# 30V_to_1V8.net
KiCad netlist of a schematic drawn in EAGLE
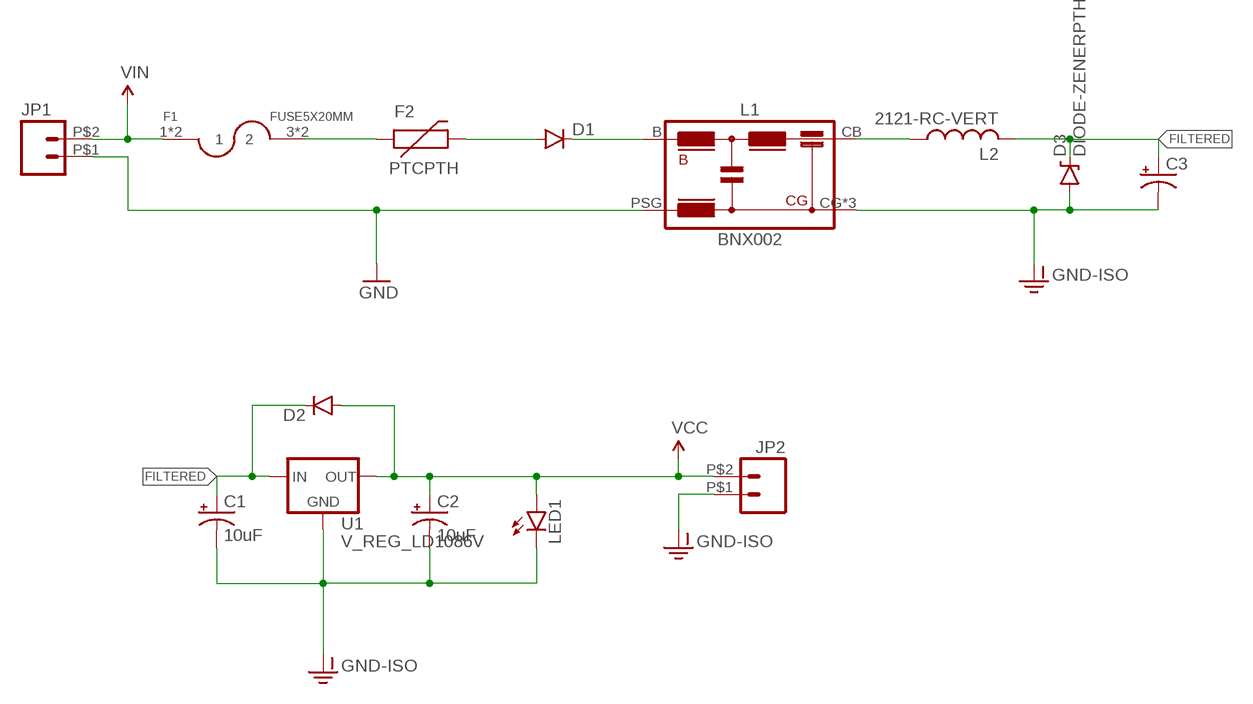
[diagram p0: schematic, sheet 1]

(export (version "E")
  (design (tool "Eeschema 10.0.6"))
  (components
    (comp (ref "C1")
      (value "10uF")
      (footprint "eagle-import:KEMET_E")
      (libsource (lib "eagle-import") (part "10UF-50V-10%(PTH)"))
    )
    (comp (ref "C2")
      (value "10uF")
      (footprint "eagle-import:KEMET_E")
      (libsource (lib "eagle-import") (part "10UF-50V-10%(PTH)"))
    )
    (comp (ref "C3")
      (value "CPOL-USE10-30")
      (footprint "eagle-import:EB30D")
      (libsource (lib "eagle-import") (part "CPOL-USE10-30"))
    )
    (comp (ref "D1")
      (value "DIODEPTH")
      (footprint "eagle-import:DIODE-1N4001")
      (libsource (lib "eagle-import") (part "DIODEPTH"))
    )
    (comp (ref "D2")
      (value "DIODEPTH")
      (footprint "eagle-import:DIODE-1N4001")
      (libsource (lib "eagle-import") (part "DIODEPTH"))
    )
    (comp (ref "D3")
      (value "DIODE-ZENERPTH")
      (footprint "eagle-import:DIODE-ZENER")
      (libsource (lib "eagle-import") (part "DIODE-ZENERPTH"))
    )
    (comp (ref "F1")
      (value "FUSE5X20MM")
      (footprint "eagle-import:FUSE_1A3399")
      (libsource (lib "eagle-import") (part "FUSE5X20MM"))
    )
    (comp (ref "F2")
      (value "PTCPTH")
      (footprint "eagle-import:PTC")
      (libsource (lib "eagle-import") (part "PTCPTH"))
    )
    (comp (ref "JP1")
      (value "M02TE-282834-2")
      (footprint "eagle-import:1X02_282834-2")
      (libsource (lib "eagle-import") (part "M02TE-282834-2"))
    )
    (comp (ref "JP2")
      (value "M02TE-282834-2")
      (footprint "eagle-import:1X02_282834-2")
      (libsource (lib "eagle-import") (part "M02TE-282834-2"))
    )
    (comp (ref "L1")
      (value "BNX002")
      (footprint "eagle-import:BNX002")
      (libsource (lib "eagle-import") (part "BNX002"))
    )
    (comp (ref "L2")
      (value "2121-RC-VERT")
      (footprint "eagle-import:2121-RC-VERT")
      (libsource (lib "eagle-import") (part "2121-RC-VERT"))
    )
    (comp (ref "LED1")
      (value "LED5MM")
      (footprint "eagle-import:LED5MM")
      (libsource (lib "eagle-import") (part "LED5MM"))
    )
    (comp (ref "U1")
      (value "V_REG_LD1086V")
      (footprint "eagle-import:TO-220-SINGLE")
      (libsource (lib "eagle-import") (part "V_REG_LD1086V"))
    )
  )
  (nets
    (net (code "1") (name "FILTERED") (class "Default")
      (node (ref "C1") (pin "+") (pinfunction "+_+") (pintype "passive"))
      (node (ref "C3") (pin "+") (pinfunction "+_+") (pintype "passive"))
      (node (ref "D2") (pin "C") (pinfunction "C_C") (pintype "passive"))
      (node (ref "D3") (pin "P$1") (pinfunction "C_P$1") (pintype "passive"))
      (node (ref "L2") (pin "2") (pinfunction "2_2") (pintype "passive"))
      (node (ref "U1") (pin "IN") (pinfunction "IN_IN") (pintype "input"))
    )
    (net (code "2") (name "GND") (class "Default")
      (node (ref "JP1") (pin "P$1") (pinfunction "1_P$1") (pintype "passive"))
      (node (ref "L1") (pin "PSG") (pinfunction "PSG_PSG") (pintype "passive"))
    )
    (net (code "3") (name "GND-ISO") (class "Default")
      (node (ref "C1") (pin "-") (pinfunction "-_-") (pintype "passive"))
      (node (ref "C2") (pin "-") (pinfunction "-_-") (pintype "passive"))
      (node (ref "C3") (pin "-") (pinfunction "-_-") (pintype "passive"))
      (node (ref "D3") (pin "P$2") (pinfunction "A_P$2") (pintype "passive"))
      (node (ref "JP2") (pin "P$1") (pinfunction "1_P$1") (pintype "passive"))
      (node (ref "L1") (pin "CG") (pinfunction "CG_CG") (pintype "passive"))
      (node (ref "L1") (pin "CG1") (pinfunction "CG_CG1") (pintype "passive"))
      (node (ref "L1") (pin "CG2") (pinfunction "CG_CG2") (pintype "passive"))
      (node (ref "LED1") (pin "K") (pinfunction "C_K") (pintype "passive"))
      (node (ref "U1") (pin "GND") (pinfunction "GND_GND") (pintype "passive"))
    )
    (net (code "4") (name "Net-(D1-PadC)") (class "Default")
      (node (ref "D1") (pin "C") (pinfunction "C_C") (pintype "passive"))
      (node (ref "L1") (pin "B") (pinfunction "B_B") (pintype "passive"))
    )
    (net (code "5") (name "Net-(F2-1)") (class "Default")
      (node (ref "F1") (pin "3") (pinfunction "2_3") (pintype "bidirectional"))
      (node (ref "F1") (pin "4") (pinfunction "2_4") (pintype "bidirectional"))
      (node (ref "F2") (pin "P$1") (pinfunction "1_P$1") (pintype "bidirectional"))
    )
    (net (code "6") (name "Net-(F2-2)") (class "Default")
      (node (ref "D1") (pin "A") (pinfunction "A_A") (pintype "passive"))
      (node (ref "F2") (pin "P$2") (pinfunction "2_P$2") (pintype "bidirectional"))
    )
    (net (code "7") (name "Net-(L1-PadCB)") (class "Default")
      (node (ref "L1") (pin "CB") (pinfunction "CB_CB") (pintype "passive"))
      (node (ref "L2") (pin "1") (pinfunction "1_1") (pintype "passive"))
    )
    (net (code "8") (name "VCC") (class "Default")
      (node (ref "C2") (pin "+") (pinfunction "+_+") (pintype "passive"))
      (node (ref "D2") (pin "A") (pinfunction "A_A") (pintype "passive"))
      (node (ref "JP2") (pin "P$2") (pinfunction "2_P$2") (pintype "passive"))
      (node (ref "LED1") (pin "A") (pinfunction "A_A") (pintype "passive"))
      (node (ref "U1") (pin "OUT") (pinfunction "OUT_OUT") (pintype "output"))
    )
    (net (code "9") (name "VIN") (class "Default")
      (node (ref "F1") (pin "1") (pinfunction "1_1") (pintype "bidirectional"))
      (node (ref "F1") (pin "2") (pinfunction "1_2") (pintype "bidirectional"))
      (node (ref "JP1") (pin "P$2") (pinfunction "2_P$2") (pintype "passive"))
    )
  )
)
